# drawingBoard.net
KiCad netlist of a schematic drawn in EAGLE
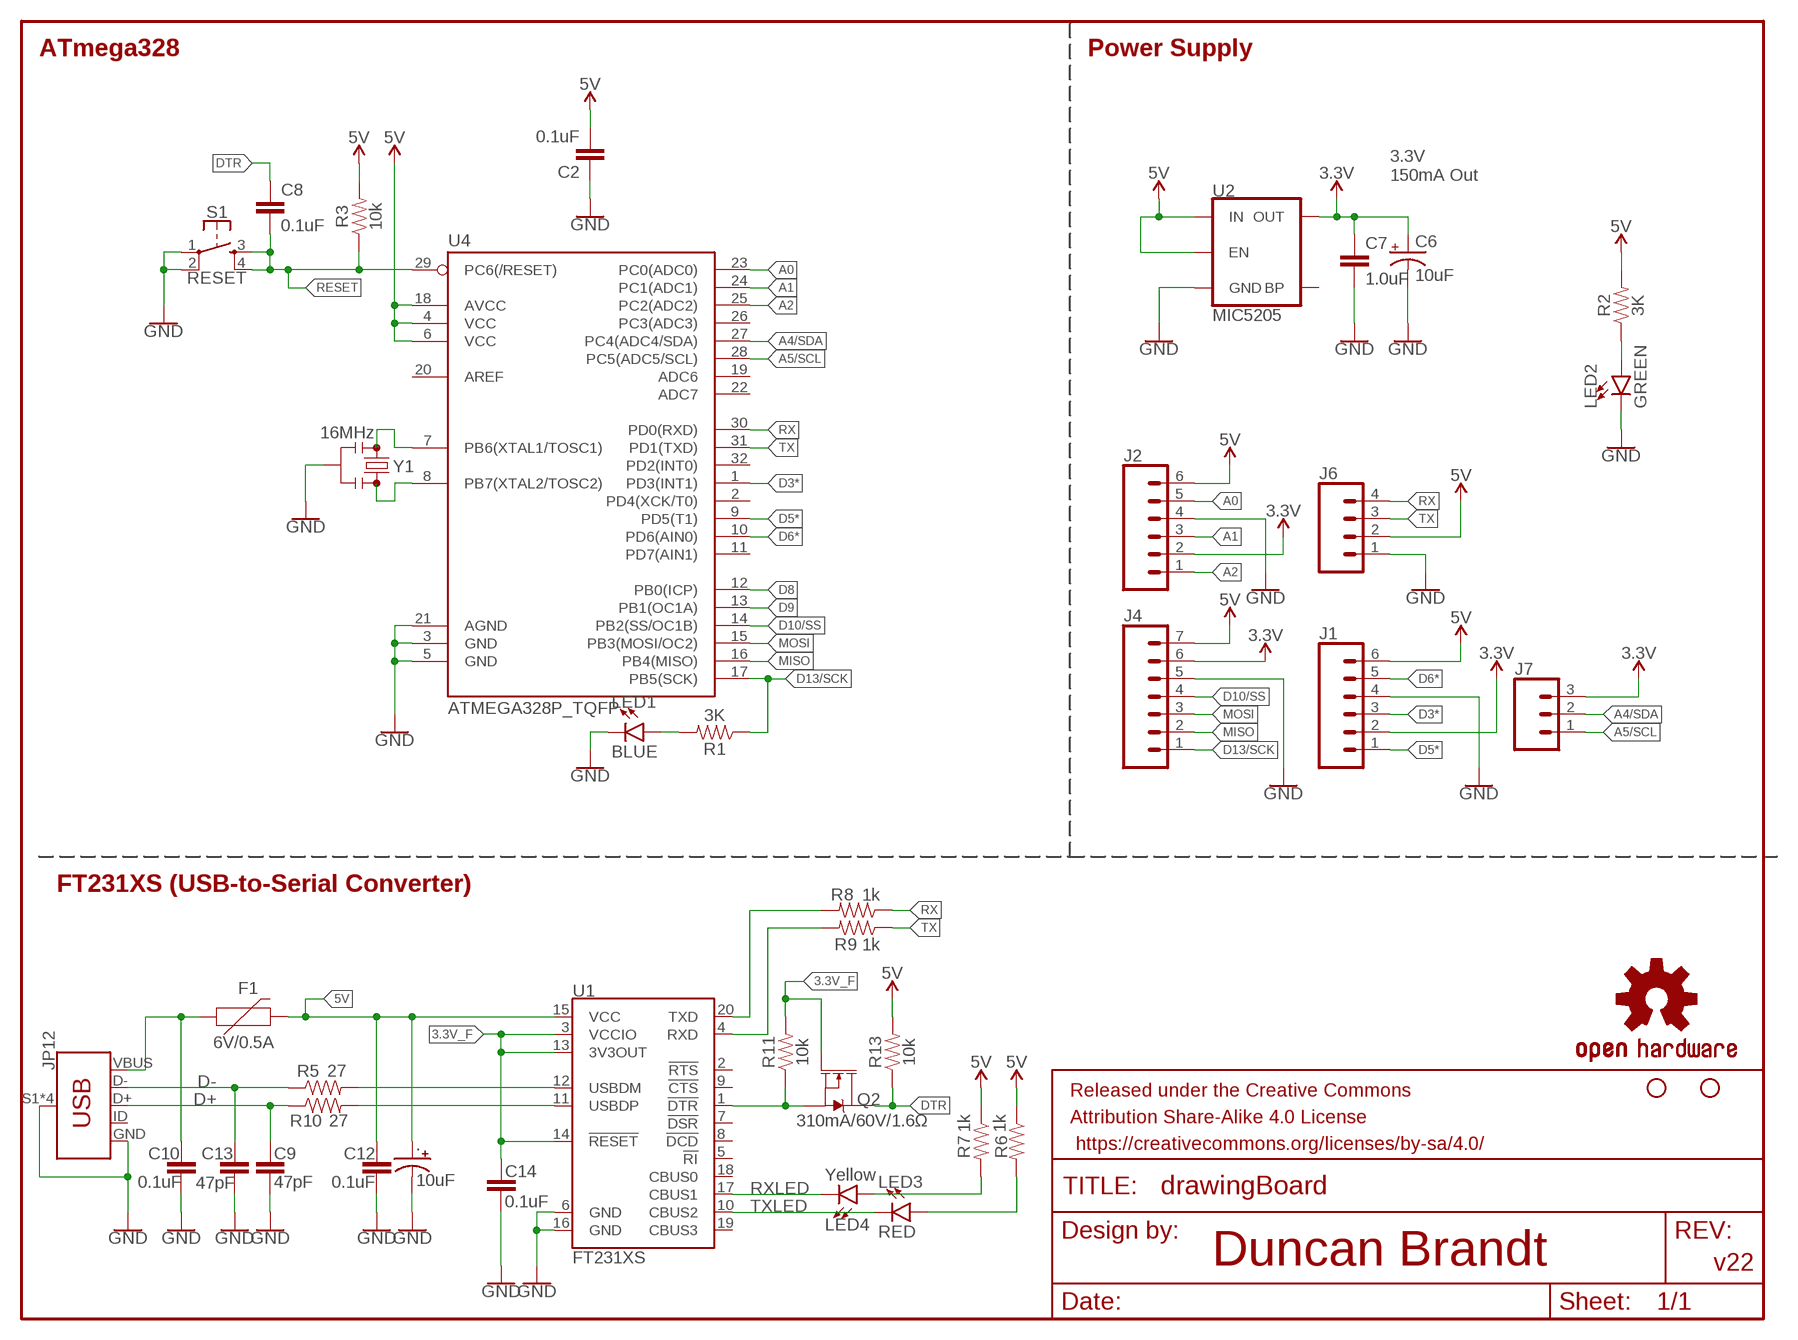
[diagram p0: schematic, sheet 1]

(export (version "E")
  (design (tool "Eeschema 10.0.6"))
  (components
    (comp (ref ".")
      (value "10uF")
      (footprint "eagle-import:EIA3216")
      (libsource (lib "eagle-import") (part "10UF-POLAR-EIA3216-16V-10%(TANT)"))
    )
    (comp (ref "C2")
      (value "0.1uF")
      (footprint "eagle-import:0603")
      (libsource (lib "eagle-import") (part "0.1UF-0603-25V-5%"))
    )
    (comp (ref "C6")
      (value "10uF")
      (footprint "eagle-import:EIA3216")
      (libsource (lib "eagle-import") (part "10UF-POLAR-EIA3216-16V-10%(TANT)"))
    )
    (comp (ref "C7")
      (value "1.0uF")
      (footprint "eagle-import:0603")
      (libsource (lib "eagle-import") (part "1.0UF-0603-16V-10%"))
    )
    (comp (ref "C8")
      (value "0.1uF")
      (footprint "eagle-import:0603")
      (libsource (lib "eagle-import") (part "0.1UF-0603-25V-5%"))
    )
    (comp (ref "C9")
      (value "47pF")
      (footprint "eagle-import:0603")
      (libsource (lib "eagle-import") (part "47PF-0603-50V-5%"))
    )
    (comp (ref "C10")
      (value "0.1uF")
      (footprint "eagle-import:0603")
      (libsource (lib "eagle-import") (part "0.1UF-0603-25V-5%"))
    )
    (comp (ref "C12")
      (value "0.1uF")
      (footprint "eagle-import:0603")
      (libsource (lib "eagle-import") (part "0.1UF-0603-25V-5%"))
    )
    (comp (ref "C13")
      (value "47pF")
      (footprint "eagle-import:0603")
      (libsource (lib "eagle-import") (part "47PF-0603-50V-5%"))
    )
    (comp (ref "C14")
      (value "0.1uF")
      (footprint "eagle-import:0603")
      (libsource (lib "eagle-import") (part "0.1UF-0603-25V-5%"))
    )
    (comp (ref "F1")
      (value "6V/0.5A")
      (footprint "eagle-import:1206")
      (libsource (lib "eagle-import") (part "PPTC_HALF-AMP"))
    )
    (comp (ref "FRAME2")
      (value "FRAME-LETTER")
      (footprint "eagle-import:CREATIVE_COMMONS")
      (libsource (lib "eagle-import") (part "FRAME-LETTER"))
    )
    (comp (ref "J1")
      (value "CONN_06SILK_FEMALE_PTH")
      (footprint "eagle-import:1X06")
      (libsource (lib "eagle-import") (part "CONN_06SILK_FEMALE_PTH"))
    )
    (comp (ref "J2")
      (value "CONN_06SILK_FEMALE_PTH")
      (footprint "eagle-import:1X06")
      (libsource (lib "eagle-import") (part "CONN_06SILK_FEMALE_PTH"))
    )
    (comp (ref "J4")
      (value "CONN_07")
      (footprint "eagle-import:1X07")
      (libsource (lib "eagle-import") (part "CONN_07"))
    )
    (comp (ref "J6")
      (value "CONN_04")
      (footprint "eagle-import:1X04")
      (libsource (lib "eagle-import") (part "CONN_04"))
    )
    (comp (ref "J7")
      (value "CONN_03")
      (footprint "eagle-import:1X03")
      (libsource (lib "eagle-import") (part "CONN_03"))
    )
    (comp (ref "JP3")
      (value "STAND-OFF")
      (footprint "eagle-import:STAND-OFF")
      (libsource (lib "eagle-import") (part "STAND-OFF"))
    )
    (comp (ref "JP6")
      (value "STAND-OFF")
      (footprint "eagle-import:STAND-OFF")
      (libsource (lib "eagle-import") (part "STAND-OFF"))
    )
    (comp (ref "JP12")
      (value "USB_MINI-B_SMT")
      (footprint "eagle-import:USB-MINIB")
      (libsource (lib "eagle-import") (part "USB_MINI-B_SMT"))
    )
    (comp (ref "LED1")
      (value "BLUE")
      (footprint "eagle-import:LED-1206")
      (libsource (lib "eagle-import") (part "LED-BLUE1206"))
    )
    (comp (ref "LED2")
      (value "GREEN")
      (footprint "eagle-import:LED-1206")
      (libsource (lib "eagle-import") (part "LED-GREEN1206"))
    )
    (comp (ref "LED3")
      (value "RED")
      (footprint "eagle-import:LED-1206")
      (libsource (lib "eagle-import") (part "LED-RED1206"))
    )
    (comp (ref "LED4")
      (value "Yellow")
      (footprint "eagle-import:LED-1206")
      (libsource (lib "eagle-import") (part "LED-YELLOW1206"))
    )
    (comp (ref "Q2")
      (value "310mA/60V/1.6Ω")
      (footprint "eagle-import:SOT323")
      (libsource (lib "eagle-import") (part "MOSFET-NCH-2N7002PW"))
    )
    (comp (ref "R1")
      (value "3K")
      (footprint "eagle-import:0603")
      (libsource (lib "eagle-import") (part "3KOHM-0603-1/10W-1%"))
    )
    (comp (ref "R2")
      (value "3K")
      (footprint "eagle-import:0603")
      (libsource (lib "eagle-import") (part "3KOHM-0603-1/10W-1%"))
    )
    (comp (ref "R3")
      (value "10k")
      (footprint "eagle-import:0603")
      (libsource (lib "eagle-import") (part "10KOHM-0603-1/10W-1%"))
    )
    (comp (ref "R5")
      (value "27")
      (footprint "eagle-import:0603")
      (libsource (lib "eagle-import") (part "27OHM-0603-1/10W-1%"))
    )
    (comp (ref "R6")
      (value "1k")
      (footprint "eagle-import:0603")
      (libsource (lib "eagle-import") (part "1KOHM-0603-1/10W-1%"))
    )
    (comp (ref "R7")
      (value "1k")
      (footprint "eagle-import:0603")
      (libsource (lib "eagle-import") (part "1KOHM-0603-1/10W-1%"))
    )
    (comp (ref "R8")
      (value "1k")
      (footprint "eagle-import:0603")
      (libsource (lib "eagle-import") (part "1KOHM-0603-1/10W-1%"))
    )
    (comp (ref "R9")
      (value "1k")
      (footprint "eagle-import:0603")
      (libsource (lib "eagle-import") (part "1KOHM-0603-1/10W-1%"))
    )
    (comp (ref "R10")
      (value "27")
      (footprint "eagle-import:0603")
      (libsource (lib "eagle-import") (part "27OHM-0603-1/10W-1%"))
    )
    (comp (ref "R11")
      (value "10k")
      (footprint "eagle-import:0603")
      (libsource (lib "eagle-import") (part "10KOHM-0603-1/10W-1%"))
    )
    (comp (ref "R13")
      (value "10k")
      (footprint "eagle-import:0603")
      (libsource (lib "eagle-import") (part "10KOHM-0603-1/10W-1%"))
    )
    (comp (ref "S1")
      (value "RESET")
      (footprint "eagle-import:TACTILE_SWITCH_SMD_5.2MM")
      (libsource (lib "eagle-import") (part "MOMENTARY-SWITCH-SPST-2-SMD-5.2MM"))
    )
    (comp (ref "U$16")
      (value "OSHW-LOGOS")
      (footprint "eagle-import:OSHW-LOGO-S")
      (libsource (lib "eagle-import") (part "OSHW-LOGOS"))
    )
    (comp (ref "U1")
      (value "FT231XS")
      (footprint "eagle-import:SSOP20_L")
      (libsource (lib "eagle-import") (part "FT231XS"))
    )
    (comp (ref "U2")
      (value "MIC5205")
      (footprint "eagle-import:SOT23-5")
      (libsource (lib "eagle-import") (part "VREG3.3V3.3V"))
    )
    (comp (ref "U4")
      (value "ATMEGA328P_TQFP")
      (footprint "eagle-import:TQFP32-08")
      (libsource (lib "eagle-import") (part "ATMEGA328P_TQFP"))
    )
    (comp (ref "Y1")
      (value "16MHz")
      (footprint "eagle-import:RESONATOR-SMD-3.2X1.3")
      (libsource (lib "eagle-import") (part "RESONATOR-16MHZSMD_3.2X1.3"))
    )
  )
  (nets
    (net (code "1") (name "/D+") (class "Default")
      (node (ref "C9") (pin "1") (pinfunction "1_1") (pintype "passive"))
      (node (ref "JP12") (pin "D+") (pinfunction "D+_D+") (pintype "bidirectional"))
      (node (ref "R10") (pin "1") (pinfunction "1_1") (pintype "passive"))
    )
    (net (code "2") (name "/D-") (class "Default")
      (node (ref "C13") (pin "1") (pinfunction "1_1") (pintype "passive"))
      (node (ref "JP12") (pin "D-") (pinfunction "D-_D-") (pintype "bidirectional"))
      (node (ref "R5") (pin "1") (pinfunction "1_1") (pintype "passive"))
    )
    (net (code "3") (name "/RXLED") (class "Default")
      (node (ref "LED4") (pin "C") (pinfunction "C_C") (pintype "passive"))
      (node (ref "U1") (pin "17") (pinfunction "CBUS1_17") (pintype "bidirectional"))
    )
    (net (code "4") (name "/TXLED") (class "Default")
      (node (ref "LED3") (pin "C") (pinfunction "C_C") (pintype "passive"))
      (node (ref "U1") (pin "10") (pinfunction "CBUS2_10") (pintype "bidirectional"))
    )
    (net (code "5") (name "3.3V") (class "Default")
      (node (ref "C6") (pin "+") (pinfunction "+_+") (pintype "passive"))
      (node (ref "C7") (pin "1") (pinfunction "1_1") (pintype "passive"))
      (node (ref "J1") (pin "2") (pinfunction "2_2") (pintype "passive"))
      (node (ref "J2") (pin "2") (pinfunction "2_2") (pintype "passive"))
      (node (ref "J4") (pin "6") (pinfunction "6_6") (pintype "passive"))
      (node (ref "J7") (pin "3") (pinfunction "3_3") (pintype "passive"))
      (node (ref "U2") (pin "5") (pinfunction "OUT_5") (pintype "passive"))
    )
    (net (code "6") (name "3.3V_F") (class "Default")
      (node (ref "C14") (pin "1") (pinfunction "1_1") (pintype "passive"))
      (node (ref "Q2") (pin "1") (pinfunction "G_1") (pintype "bidirectional"))
      (node (ref "R11") (pin "2") (pinfunction "2_2") (pintype "passive"))
      (node (ref "U1") (pin "13") (pinfunction "3V3OUT_13") (pintype "bidirectional"))
      (node (ref "U1") (pin "14") (pinfunction "~{RESET}_14") (pintype "bidirectional"))
      (node (ref "U1") (pin "3") (pinfunction "VCCIO_3") (pintype "bidirectional"))
    )
    (net (code "7") (name "5V") (class "Default")
      (node (ref ".") (pin "+") (pinfunction "+_+") (pintype "passive"))
      (node (ref "C12") (pin "1") (pinfunction "1_1") (pintype "passive"))
      (node (ref "C2") (pin "2") (pinfunction "2_2") (pintype "passive"))
      (node (ref "F1") (pin "2") (pinfunction "2_2") (pintype "bidirectional"))
      (node (ref "J1") (pin "6") (pinfunction "6_6") (pintype "passive"))
      (node (ref "J2") (pin "6") (pinfunction "6_6") (pintype "passive"))
      (node (ref "J4") (pin "7") (pinfunction "7_7") (pintype "passive"))
      (node (ref "J6") (pin "2") (pinfunction "2_2") (pintype "passive"))
      (node (ref "R13") (pin "2") (pinfunction "2_2") (pintype "passive"))
      (node (ref "R2") (pin "2") (pinfunction "2_2") (pintype "passive"))
      (node (ref "R3") (pin "2") (pinfunction "2_2") (pintype "passive"))
      (node (ref "R6") (pin "1") (pinfunction "1_1") (pintype "passive"))
      (node (ref "R7") (pin "1") (pinfunction "1_1") (pintype "passive"))
      (node (ref "U1") (pin "15") (pinfunction "VCC_15") (pintype "bidirectional"))
      (node (ref "U2") (pin "1") (pinfunction "IN_1") (pintype "input"))
      (node (ref "U2") (pin "3") (pinfunction "EN_3") (pintype "input"))
      (node (ref "U4") (pin "18") (pinfunction "AVCC_18") (pintype "bidirectional"))
      (node (ref "U4") (pin "4") (pinfunction "VCC_4") (pintype "bidirectional"))
      (node (ref "U4") (pin "6") (pinfunction "VCC_6") (pintype "bidirectional"))
    )
    (net (code "8") (name "A0") (class "Default")
      (node (ref "J2") (pin "5") (pinfunction "5_5") (pintype "passive"))
      (node (ref "U4") (pin "23") (pinfunction "PC0(ADC0)_23") (pintype "bidirectional"))
    )
    (net (code "9") (name "A1") (class "Default")
      (node (ref "J2") (pin "3") (pinfunction "3_3") (pintype "passive"))
      (node (ref "U4") (pin "24") (pinfunction "PC1(ADC1)_24") (pintype "bidirectional"))
    )
    (net (code "10") (name "A2") (class "Default")
      (node (ref "J2") (pin "1") (pinfunction "1_1") (pintype "passive"))
      (node (ref "U4") (pin "25") (pinfunction "PC2(ADC2)_25") (pintype "bidirectional"))
    )
    (net (code "11") (name "A4{slash}SDA") (class "Default")
      (node (ref "J7") (pin "2") (pinfunction "2_2") (pintype "passive"))
      (node (ref "U4") (pin "27") (pinfunction "PC4(ADC4/SDA)_27") (pintype "bidirectional"))
    )
    (net (code "12") (name "A5{slash}SCL") (class "Default")
      (node (ref "J7") (pin "1") (pinfunction "1_1") (pintype "passive"))
      (node (ref "U4") (pin "28") (pinfunction "PC5(ADC5/SCL)_28") (pintype "bidirectional"))
    )
    (net (code "13") (name "D3*") (class "Default")
      (node (ref "J1") (pin "3") (pinfunction "3_3") (pintype "passive"))
      (node (ref "U4") (pin "1") (pinfunction "PD3(INT1)_1") (pintype "bidirectional"))
    )
    (net (code "14") (name "D5*") (class "Default")
      (node (ref "J1") (pin "1") (pinfunction "1_1") (pintype "passive"))
      (node (ref "U4") (pin "9") (pinfunction "PD5(T1)_9") (pintype "bidirectional"))
    )
    (net (code "15") (name "D6*") (class "Default")
      (node (ref "J1") (pin "5") (pinfunction "5_5") (pintype "passive"))
      (node (ref "U4") (pin "10") (pinfunction "PD6(AIN0)_10") (pintype "bidirectional"))
    )
    (net (code "16") (name "D8") (class "Default")
      (node (ref "U4") (pin "12") (pinfunction "PB0(ICP)_12") (pintype "bidirectional"))
    )
    (net (code "17") (name "D9") (class "Default")
      (node (ref "U4") (pin "13") (pinfunction "PB1(OC1A)_13") (pintype "bidirectional"))
    )
    (net (code "18") (name "D10{slash}SS") (class "Default")
      (node (ref "J4") (pin "4") (pinfunction "4_4") (pintype "passive"))
      (node (ref "U4") (pin "14") (pinfunction "PB2(SS/OC1B)_14") (pintype "bidirectional"))
    )
    (net (code "19") (name "D13{slash}SCK") (class "Default")
      (node (ref "J4") (pin "1") (pinfunction "1_1") (pintype "passive"))
      (node (ref "R1") (pin "1") (pinfunction "1_1") (pintype "passive"))
      (node (ref "U4") (pin "17") (pinfunction "PB5(SCK)_17") (pintype "bidirectional"))
    )
    (net (code "20") (name "DTR") (class "Default")
      (node (ref "C8") (pin "1") (pinfunction "1_1") (pintype "passive"))
      (node (ref "Q2") (pin "3") (pinfunction "D_3") (pintype "bidirectional"))
      (node (ref "R13") (pin "1") (pinfunction "1_1") (pintype "passive"))
    )
    (net (code "21") (name "GND") (class "Default")
      (node (ref ".") (pin "-") (pinfunction "-_-") (pintype "passive"))
      (node (ref "C10") (pin "2") (pinfunction "2_2") (pintype "passive"))
      (node (ref "C12") (pin "2") (pinfunction "2_2") (pintype "passive"))
      (node (ref "C13") (pin "2") (pinfunction "2_2") (pintype "passive"))
      (node (ref "C14") (pin "2") (pinfunction "2_2") (pintype "passive"))
      (node (ref "C2") (pin "1") (pinfunction "1_1") (pintype "passive"))
      (node (ref "C6") (pin "-") (pinfunction "-_-") (pintype "passive"))
      (node (ref "C7") (pin "2") (pinfunction "2_2") (pintype "passive"))
      (node (ref "C9") (pin "2") (pinfunction "2_2") (pintype "passive"))
      (node (ref "J1") (pin "4") (pinfunction "4_4") (pintype "passive"))
      (node (ref "J2") (pin "4") (pinfunction "4_4") (pintype "passive"))
      (node (ref "J4") (pin "5") (pinfunction "5_5") (pintype "passive"))
      (node (ref "J6") (pin "1") (pinfunction "1_1") (pintype "passive"))
      (node (ref "JP12") (pin "GND") (pinfunction "GND_GND") (pintype "power_in"))
      (node (ref "JP12") (pin "S1") (pinfunction "SHIELD_S1") (pintype "bidirectional"))
      (node (ref "JP12") (pin "S2") (pinfunction "SHIELD_S2") (pintype "bidirectional"))
      (node (ref "JP12") (pin "S3") (pinfunction "SHIELD_S3") (pintype "bidirectional"))
      (node (ref "JP12") (pin "S4") (pinfunction "SHIELD_S4") (pintype "bidirectional"))
      (node (ref "LED1") (pin "C") (pinfunction "C_C") (pintype "passive"))
      (node (ref "LED2") (pin "C") (pinfunction "C_C") (pintype "passive"))
      (node (ref "S1") (pin "1") (pinfunction "1_1") (pintype "passive"))
      (node (ref "S1") (pin "2") (pinfunction "2_2") (pintype "passive"))
      (node (ref "U1") (pin "16") (pinfunction "GND_16") (pintype "bidirectional"))
      (node (ref "U1") (pin "6") (pinfunction "GND_6") (pintype "bidirectional"))
      (node (ref "U2") (pin "2") (pinfunction "GND_2") (pintype "input"))
      (node (ref "U4") (pin "21") (pinfunction "AGND_21") (pintype "bidirectional"))
      (node (ref "U4") (pin "3") (pinfunction "GND_3") (pintype "bidirectional"))
      (node (ref "U4") (pin "5") (pinfunction "GND_5") (pintype "bidirectional"))
      (node (ref "Y1") (pin "2") (pinfunction "2_2") (pintype "passive"))
    )
    (net (code "22") (name "MISO") (class "Default")
      (node (ref "J4") (pin "2") (pinfunction "2_2") (pintype "passive"))
      (node (ref "U4") (pin "16") (pinfunction "PB4(MISO)_16") (pintype "bidirectional"))
    )
    (net (code "23") (name "MOSI") (class "Default")
      (node (ref "J4") (pin "3") (pinfunction "3_3") (pintype "passive"))
      (node (ref "U4") (pin "15") (pinfunction "PB3(MOSI/OC2)_15") (pintype "bidirectional"))
    )
    (net (code "24") (name "Net-(C10-Pad1)") (class "Default")
      (node (ref "C10") (pin "1") (pinfunction "1_1") (pintype "passive"))
      (node (ref "F1") (pin "1") (pinfunction "1_1") (pintype "bidirectional"))
      (node (ref "JP12") (pin "VBUS") (pinfunction "VBUS_VBUS") (pintype "power_in"))
    )
    (net (code "25") (name "Net-(LED1-PadA)") (class "Default")
      (node (ref "LED1") (pin "A") (pinfunction "A_A") (pintype "passive"))
      (node (ref "R1") (pin "2") (pinfunction "2_2") (pintype "passive"))
    )
    (net (code "26") (name "Net-(LED2-PadA)") (class "Default")
      (node (ref "LED2") (pin "A") (pinfunction "A_A") (pintype "passive"))
      (node (ref "R2") (pin "1") (pinfunction "1_1") (pintype "passive"))
    )
    (net (code "27") (name "Net-(LED3-PadA)") (class "Default")
      (node (ref "LED3") (pin "A") (pinfunction "A_A") (pintype "passive"))
      (node (ref "R6") (pin "2") (pinfunction "2_2") (pintype "passive"))
    )
    (net (code "28") (name "Net-(LED4-PadA)") (class "Default")
      (node (ref "LED4") (pin "A") (pinfunction "A_A") (pintype "passive"))
      (node (ref "R7") (pin "2") (pinfunction "2_2") (pintype "passive"))
    )
    (net (code "29") (name "Net-(Q2-S)") (class "Default")
      (node (ref "Q2") (pin "2") (pinfunction "S_2") (pintype "bidirectional"))
      (node (ref "R11") (pin "1") (pinfunction "1_1") (pintype "passive"))
      (node (ref "U1") (pin "1") (pinfunction "~{DTR}_1") (pintype "bidirectional"))
    )
    (net (code "30") (name "Net-(U1-RXD)") (class "Default")
      (node (ref "R9") (pin "2") (pinfunction "2_2") (pintype "passive"))
      (node (ref "U1") (pin "4") (pinfunction "RXD_4") (pintype "bidirectional"))
    )
    (net (code "31") (name "Net-(U1-TXD)") (class "Default")
      (node (ref "R8") (pin "2") (pinfunction "2_2") (pintype "passive"))
      (node (ref "U1") (pin "20") (pinfunction "TXD_20") (pintype "bidirectional"))
    )
    (net (code "32") (name "Net-(U1-USBDM)") (class "Default")
      (node (ref "R5") (pin "2") (pinfunction "2_2") (pintype "passive"))
      (node (ref "U1") (pin "12") (pinfunction "USBDM_12") (pintype "bidirectional"))
    )
    (net (code "33") (name "Net-(U1-USBDP)") (class "Default")
      (node (ref "R10") (pin "2") (pinfunction "2_2") (pintype "passive"))
      (node (ref "U1") (pin "11") (pinfunction "USBDP_11") (pintype "bidirectional"))
    )
    (net (code "34") (name "Net-(U4-PB6(XTAL1{slash}TOSC1))") (class "Default")
      (node (ref "U4") (pin "7") (pinfunction "PB6(XTAL1/TOSC1)_7") (pintype "bidirectional"))
      (node (ref "Y1") (pin "1") (pinfunction "1_1") (pintype "passive"))
    )
    (net (code "35") (name "Net-(U4-PB7(XTAL2{slash}TOSC2))") (class "Default")
      (node (ref "U4") (pin "8") (pinfunction "PB7(XTAL2/TOSC2)_8") (pintype "bidirectional"))
      (node (ref "Y1") (pin "3") (pinfunction "3_3") (pintype "passive"))
    )
    (net (code "36") (name "RESET") (class "Default")
      (node (ref "C8") (pin "2") (pinfunction "2_2") (pintype "passive"))
      (node (ref "R3") (pin "1") (pinfunction "1_1") (pintype "passive"))
      (node (ref "S1") (pin "3") (pinfunction "3_3") (pintype "passive"))
      (node (ref "S1") (pin "4") (pinfunction "4_4") (pintype "passive"))
      (node (ref "U4") (pin "29") (pinfunction "PC6(/RESET)_29") (pintype "bidirectional"))
    )
    (net (code "37") (name "RX") (class "Default")
      (node (ref "J6") (pin "4") (pinfunction "4_4") (pintype "passive"))
      (node (ref "R8") (pin "1") (pinfunction "1_1") (pintype "passive"))
      (node (ref "U4") (pin "30") (pinfunction "PD0(RXD)_30") (pintype "bidirectional"))
    )
    (net (code "38") (name "TX") (class "Default")
      (node (ref "J6") (pin "3") (pinfunction "3_3") (pintype "passive"))
      (node (ref "R9") (pin "1") (pinfunction "1_1") (pintype "passive"))
      (node (ref "U4") (pin "31") (pinfunction "PD1(TXD)_31") (pintype "bidirectional"))
    )
    (net (code "39") (name "unconnected-(JP12-PadID)") (class "Default")
      (node (ref "JP12") (pin "ID") (pinfunction "ID_ID") (pintype "bidirectional"))
    )
    (net (code "40") (name "unconnected-(U1-CBUS0-Pad18)") (class "Default")
      (node (ref "U1") (pin "18") (pinfunction "CBUS0_18") (pintype "bidirectional"))
    )
    (net (code "41") (name "unconnected-(U1-CBUS3-Pad19)") (class "Default")
      (node (ref "U1") (pin "19") (pinfunction "CBUS3_19") (pintype "bidirectional"))
    )
    (net (code "42") (name "unconnected-(U1-~{CTS}-Pad9)") (class "Default")
      (node (ref "U1") (pin "9") (pinfunction "~{CTS}_9") (pintype "bidirectional"))
    )
    (net (code "43") (name "unconnected-(U1-~{DCD}-Pad8)") (class "Default")
      (node (ref "U1") (pin "8") (pinfunction "~{DCD}_8") (pintype "bidirectional"))
    )
    (net (code "44") (name "unconnected-(U1-~{DSR}-Pad7)") (class "Default")
      (node (ref "U1") (pin "7") (pinfunction "~{DSR}_7") (pintype "bidirectional"))
    )
    (net (code "45") (name "unconnected-(U1-~{RI}-Pad5)") (class "Default")
      (node (ref "U1") (pin "5") (pinfunction "~{RI}_5") (pintype "bidirectional"))
    )
    (net (code "46") (name "unconnected-(U1-~{RTS}-Pad2)") (class "Default")
      (node (ref "U1") (pin "2") (pinfunction "~{RTS}_2") (pintype "bidirectional"))
    )
    (net (code "47") (name "unconnected-(U2-BP-Pad4)") (class "Default")
      (node (ref "U2") (pin "4") (pinfunction "BP_4") (pintype "input"))
    )
    (net (code "48") (name "unconnected-(U4-ADC6-Pad19)") (class "Default")
      (node (ref "U4") (pin "19") (pinfunction "ADC6_19") (pintype "bidirectional"))
    )
    (net (code "49") (name "unconnected-(U4-ADC7-Pad22)") (class "Default")
      (node (ref "U4") (pin "22") (pinfunction "ADC7_22") (pintype "bidirectional"))
    )
    (net (code "50") (name "unconnected-(U4-AREF-Pad20)") (class "Default")
      (node (ref "U4") (pin "20") (pinfunction "AREF_20") (pintype "bidirectional"))
    )
    (net (code "51") (name "unconnected-(U4-PC3(ADC3)-Pad26)") (class "Default")
      (node (ref "U4") (pin "26") (pinfunction "PC3(ADC3)_26") (pintype "bidirectional"))
    )
    (net (code "52") (name "unconnected-(U4-PD2(INT0)-Pad32)") (class "Default")
      (node (ref "U4") (pin "32") (pinfunction "PD2(INT0)_32") (pintype "bidirectional"))
    )
    (net (code "53") (name "unconnected-(U4-PD4(XCK{slash}T0)-Pad2)") (class "Default")
      (node (ref "U4") (pin "2") (pinfunction "PD4(XCK/T0)_2") (pintype "bidirectional"))
    )
    (net (code "54") (name "unconnected-(U4-PD7(AIN1)-Pad11)") (class "Default")
      (node (ref "U4") (pin "11") (pinfunction "PD7(AIN1)_11") (pintype "bidirectional"))
    )
  )
)
